# Telemetry_Unit.net
KiCad netlist of a schematic drawn in EAGLE
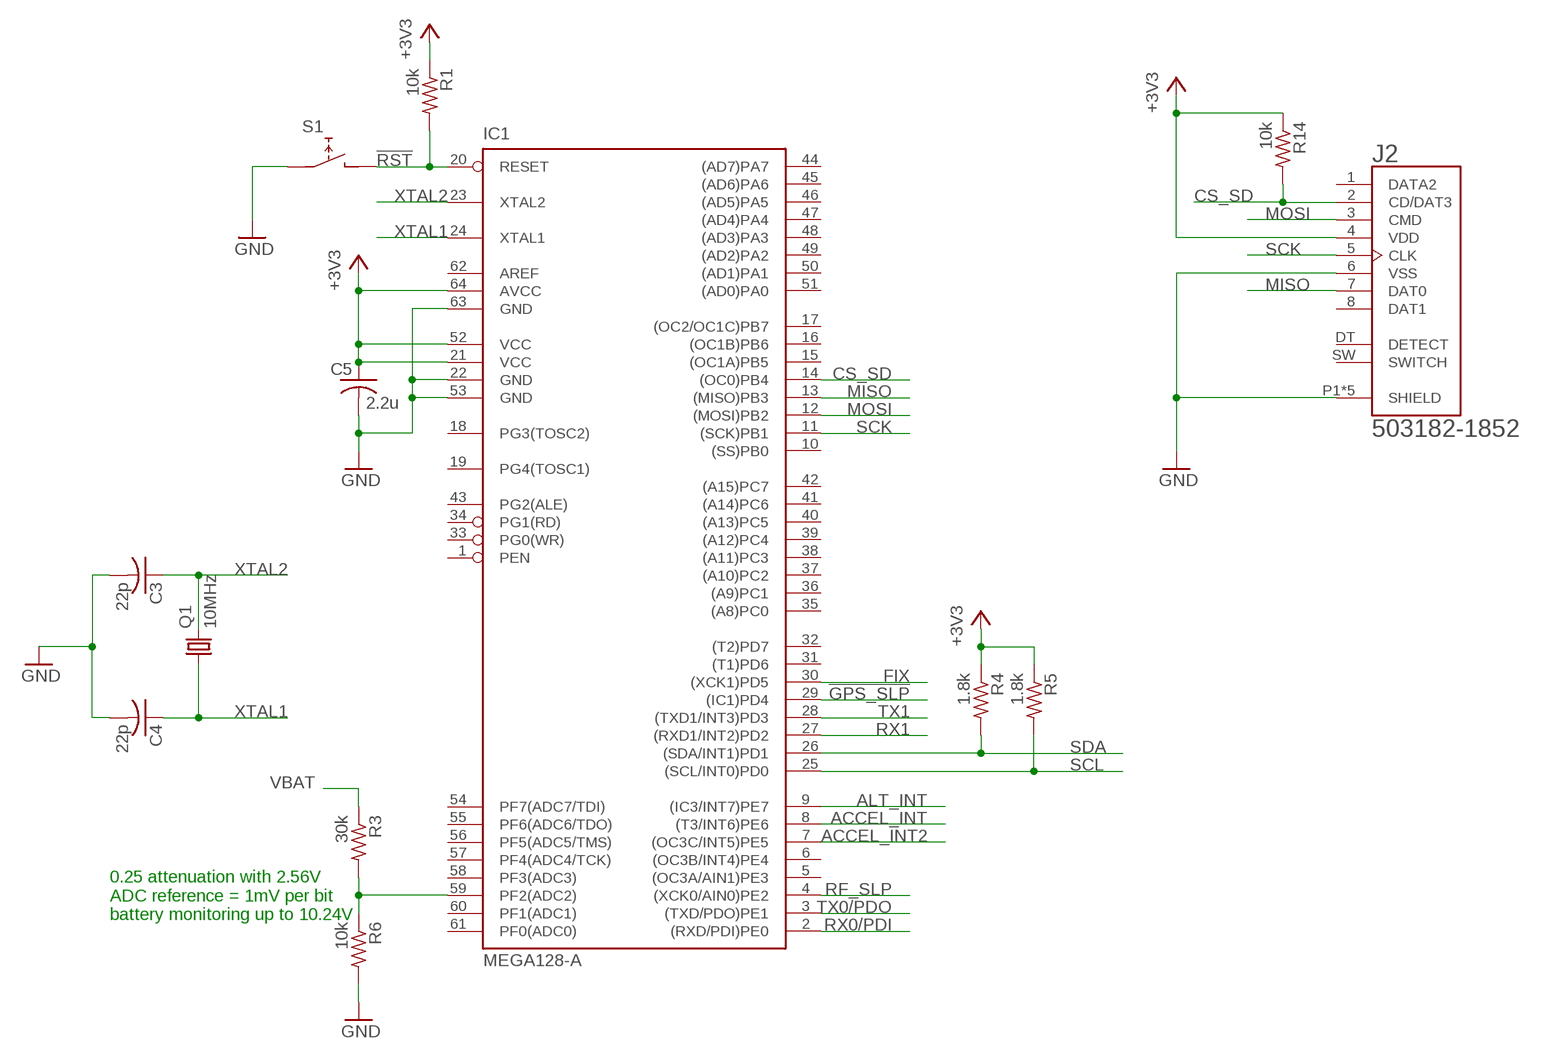
[diagram p0: schematic, sheet 1]
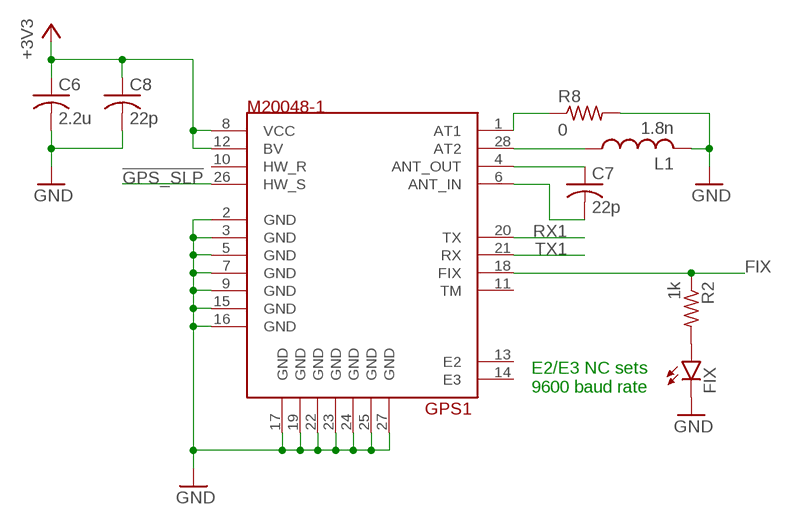
[diagram p1: schematic, sheet 2]
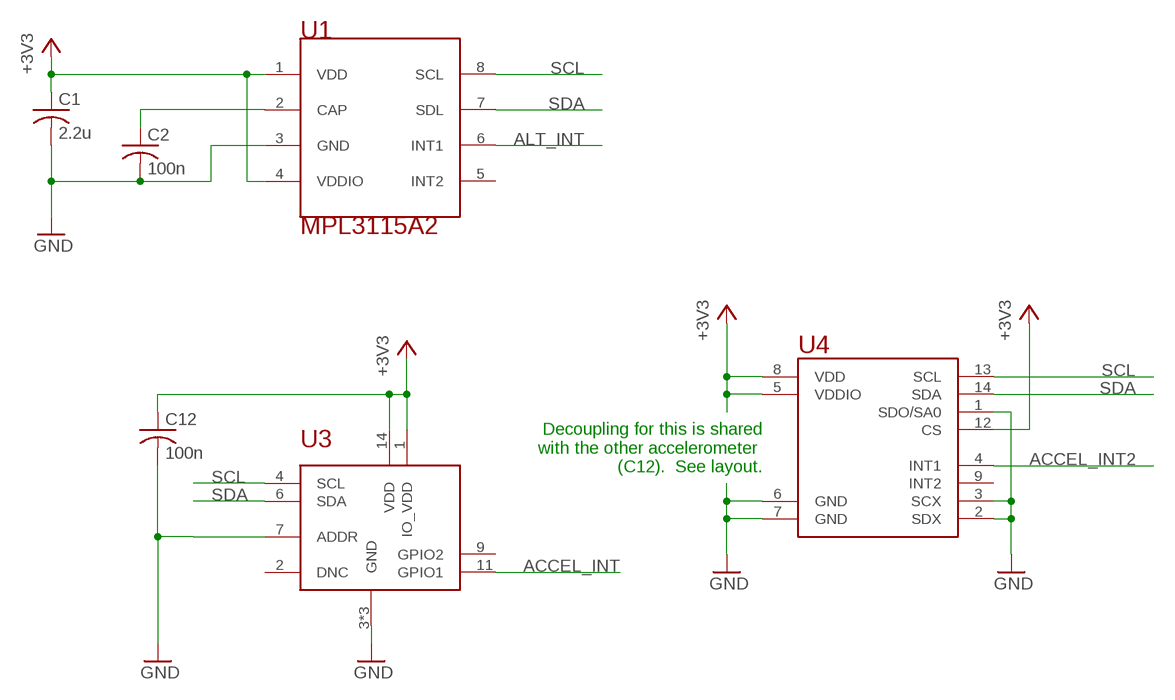
[diagram p2: schematic, sheet 3]
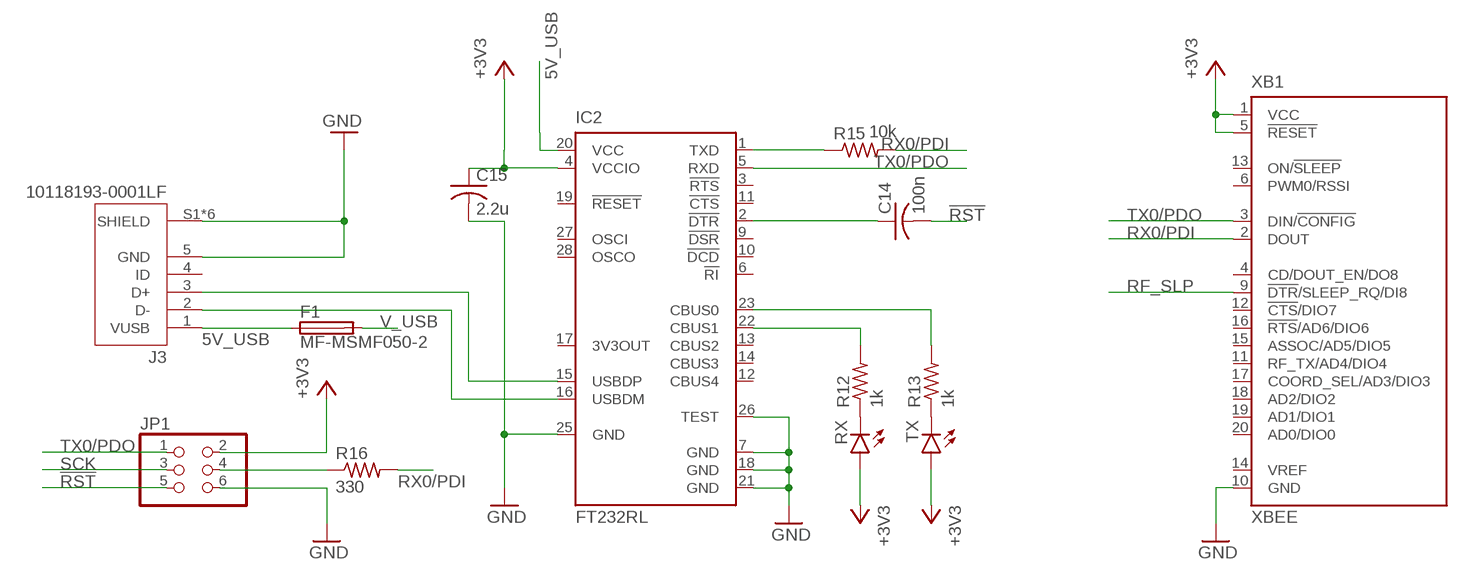
[diagram p3: schematic, sheet 4]
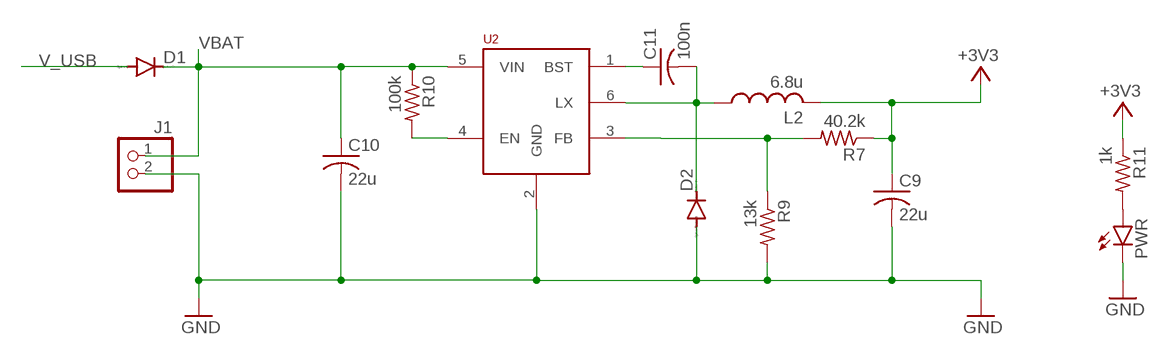
[diagram p4: schematic, sheet 5]

(export (version "E")
  (design (tool "Eeschema 10.0.6"))
  (components
    (comp (ref "C9")
      (value "22u")
      (footprint "eagle-import:C0805")
      (libsource (lib "eagle-import") (part "C-USC0805"))
    )
    (comp (ref "C10")
      (value "22u")
      (footprint "eagle-import:C0805")
      (libsource (lib "eagle-import") (part "C-USC0805"))
    )
    (comp (ref "C11")
      (value "100n")
      (footprint "eagle-import:C0603")
      (libsource (lib "eagle-import") (part "C-USC0603"))
    )
    (comp (ref "D1")
      (value "DIODE-SOD123")
      (footprint "eagle-import:SOD123")
      (libsource (lib "eagle-import") (part "DIODE-SOD123"))
    )
    (comp (ref "D2")
      (value "DIODE-SOD123")
      (footprint "eagle-import:SOD123")
      (libsource (lib "eagle-import") (part "DIODE-SOD123"))
    )
    (comp (ref "J1")
      (value "ST_2X1")
      (footprint "eagle-import:ST_2X1")
      (libsource (lib "eagle-import") (part "ST_2X1"))
    )
    (comp (ref "L2")
      (value "6.8u")
      (footprint "eagle-import:L1210")
      (libsource (lib "eagle-import") (part "L_SMALLL1210"))
    )
    (comp (ref "PWR")
      (value "LEDCHIP-LED0603")
      (footprint "eagle-import:CHIP-LED0603")
      (libsource (lib "eagle-import") (part "LEDCHIP-LED0603"))
    )
    (comp (ref "R7")
      (value "40.2k")
      (footprint "eagle-import:R0603")
      (libsource (lib "eagle-import") (part "resistor_348_R-US_R0603"))
    )
    (comp (ref "R9")
      (value "13k")
      (footprint "eagle-import:R0603")
      (libsource (lib "eagle-import") (part "resistor_348_R-US_R0603"))
    )
    (comp (ref "R10")
      (value "100k")
      (footprint "eagle-import:R0603")
      (libsource (lib "eagle-import") (part "resistor_348_R-US_R0603"))
    )
    (comp (ref "R11")
      (value "1k")
      (footprint "eagle-import:R0603")
      (libsource (lib "eagle-import") (part "resistor_348_R-US_R0603"))
    )
    (comp (ref "U2")
      (value "AOZ1280")
      (footprint "eagle-import:TSOT23-6")
      (libsource (lib "eagle-import") (part "AOZ1280"))
    )
    (comp (ref "C14")
      (value "100n")
      (footprint "eagle-import:C0603")
      (libsource (lib "eagle-import") (part "C-USC0603"))
    )
    (comp (ref "C15")
      (value "2.2u")
      (footprint "eagle-import:C0603")
      (libsource (lib "eagle-import") (part "C-USC0603"))
    )
    (comp (ref "F1")
      (value "MF-MSMF050-2")
      (footprint "eagle-import:FUSM1812X02")
      (fields (field (name "MF") "Bourns"))
      (libsource (lib "eagle-import") (part "MF-MSMF050-2"))
    )
    (comp (ref "IC2")
      (value "FT232RL")
      (footprint "eagle-import:SSOP28")
      (libsource (lib "eagle-import") (part "FT232RL"))
    )
    (comp (ref "J3")
      (value "10118193-0001LF")
      (footprint "eagle-import:FCI_10118193-0001LF")
      (fields (field (name "DIGI-KEY_PART_NUMBER") "609-4616-1-ND") (field (name "MF") "Amphenol ICC"))
      (libsource (lib "eagle-import") (part "10118193-0001LF"))
    )
    (comp (ref "JP1")
      (value "PINHD-2X3")
      (footprint "eagle-import:2X03")
      (libsource (lib "eagle-import") (part "PINHD-2X3"))
    )
    (comp (ref "R12")
      (value "1k")
      (footprint "eagle-import:R0603")
      (libsource (lib "eagle-import") (part "R-US_R0603"))
    )
    (comp (ref "R13")
      (value "1k")
      (footprint "eagle-import:R0603")
      (libsource (lib "eagle-import") (part "R-US_R0603"))
    )
    (comp (ref "R15")
      (value "10k")
      (footprint "eagle-import:R0603")
      (libsource (lib "eagle-import") (part "resistor_348_R-US_R0603"))
    )
    (comp (ref "R16")
      (value "330")
      (footprint "eagle-import:R0603")
      (libsource (lib "eagle-import") (part "resistor_348_R-US_R0603"))
    )
    (comp (ref "RX")
      (value "LEDCHIP-LED0603")
      (footprint "eagle-import:CHIP-LED0603")
      (libsource (lib "eagle-import") (part "LEDCHIP-LED0603"))
    )
    (comp (ref "TX")
      (value "LEDCHIP-LED0603")
      (footprint "eagle-import:CHIP-LED0603")
      (libsource (lib "eagle-import") (part "LEDCHIP-LED0603"))
    )
    (comp (ref "XB1")
      (value "XBEE")
      (footprint "eagle-import:XBEE")
      (fields (field (name "MPN") "XBP24-Z7UIT-004"))
      (libsource (lib "eagle-import") (part "XBEE"))
    )
    (comp (ref "C3")
      (value "22p")
      (footprint "eagle-import:C0603")
      (libsource (lib "eagle-import") (part "C-USC0603"))
    )
    (comp (ref "C4")
      (value "22p")
      (footprint "eagle-import:C0603")
      (libsource (lib "eagle-import") (part "C-USC0603"))
    )
    (comp (ref "C5")
      (value "2.2u")
      (footprint "eagle-import:C0603")
      (libsource (lib "eagle-import") (part "C-USC0603"))
    )
    (comp (ref "IC1")
      (value "MEGA128-A")
      (footprint "eagle-import:TQFP64")
      (fields (field (name "MPN") "ATMEGA128-16AU"))
      (libsource (lib "eagle-import") (part "MEGA128-A"))
    )
    (comp (ref "J2")
      (value "503182-1852")
      (footprint "eagle-import:MOLEX_503182-1852")
      (fields
        (field (name "DIGI-KEY_PART_NUMBER") "WM12834CT-ND")
        (field (name "MF") "Molex, LLC")
        (field (name "MP") "5031821852")
      )
      (libsource (lib "eagle-import") (part "503182-1852"))
    )
    (comp (ref "Q1")
      (value "10MHz")
      (footprint "eagle-import:3.2X2.5_KX-7")
      (libsource (lib "eagle-import") (part "KX-7"))
    )
    (comp (ref "R1")
      (value "10k")
      (footprint "eagle-import:R0603")
      (libsource (lib "eagle-import") (part "resistor_348_R-US_R0603"))
    )
    (comp (ref "R3")
      (value "30k")
      (footprint "eagle-import:R0603")
      (libsource (lib "eagle-import") (part "resistor_348_R-US_R0603"))
    )
    (comp (ref "R4")
      (value "1.8k")
      (footprint "eagle-import:R0603")
      (libsource (lib "eagle-import") (part "resistor_348_R-US_R0603"))
    )
    (comp (ref "R5")
      (value "1.8k")
      (footprint "eagle-import:R0603")
      (libsource (lib "eagle-import") (part "resistor_348_R-US_R0603"))
    )
    (comp (ref "R6")
      (value "10k")
      (footprint "eagle-import:R0603")
      (libsource (lib "eagle-import") (part "resistor_348_R-US_R0603"))
    )
    (comp (ref "R14")
      (value "10k")
      (footprint "eagle-import:R0603")
      (libsource (lib "eagle-import") (part "resistor_348_R-US_R0603"))
    )
    (comp (ref "S1")
      (value "TACT_SW_4.5MM")
      (footprint "eagle-import:TACT_SW_4.5MM")
      (libsource (lib "eagle-import") (part "TACT_SW_4.5MM"))
    )
    (comp (ref "C6")
      (value "2.2u")
      (footprint "eagle-import:C0603")
      (libsource (lib "eagle-import") (part "C-USC0603"))
    )
    (comp (ref "C7")
      (value "22p")
      (footprint "eagle-import:C0603")
      (libsource (lib "eagle-import") (part "C-USC0603"))
    )
    (comp (ref "C8")
      (value "22p")
      (footprint "eagle-import:C0603")
      (libsource (lib "eagle-import") (part "C-USC0603"))
    )
    (comp (ref "FIX")
      (value "LEDCHIP-LED0603")
      (footprint "eagle-import:CHIP-LED0603")
      (libsource (lib "eagle-import") (part "LEDCHIP-LED0603"))
    )
    (comp (ref "GPS1")
      (value "M20048-1")
      (footprint "eagle-import:M20048-1")
      (libsource (lib "eagle-import") (part "M20048-1"))
    )
    (comp (ref "L1")
      (value "1.8n")
      (footprint "eagle-import:L0603")
      (libsource (lib "eagle-import") (part "L_SMALLL0603"))
    )
    (comp (ref "R2")
      (value "1k")
      (footprint "eagle-import:R0603")
      (libsource (lib "eagle-import") (part "resistor_348_R-US_R0603"))
    )
    (comp (ref "R8")
      (value "0")
      (footprint "eagle-import:R0603")
      (libsource (lib "eagle-import") (part "resistor_348_R-US_R0603"))
    )
    (comp (ref "C1")
      (value "2.2u")
      (footprint "eagle-import:C0603")
      (libsource (lib "eagle-import") (part "C-USC0603"))
    )
    (comp (ref "C2")
      (value "100n")
      (footprint "eagle-import:C0603")
      (libsource (lib "eagle-import") (part "C-USC0603"))
    )
    (comp (ref "C12")
      (value "100n")
      (footprint "eagle-import:C0603")
      (libsource (lib "eagle-import") (part "C-USC0603"))
    )
    (comp (ref "U1")
      (value "MPL3115A2")
      (footprint "eagle-import:LGA8")
      (libsource (lib "eagle-import") (part "MPL3115A2"))
    )
    (comp (ref "U3")
      (value "KMX63-1055")
      (footprint "eagle-import:LGA16_3X3")
      (libsource (lib "eagle-import") (part "KMX63-1055"))
    )
    (comp (ref "U4")
      (value "LSM6DS3")
      (footprint "eagle-import:14-LGA")
      (libsource (lib "eagle-import") (part "LSM6DS3"))
    )
  )
  (nets
    (net (code "1") (name "+3V3") (class "Default")
      (node (ref "C1") (pin "1") (pinfunction "1_1") (pintype "passive"))
      (node (ref "C12") (pin "1") (pinfunction "1_1") (pintype "passive"))
      (node (ref "C15") (pin "1") (pinfunction "1_1") (pintype "passive"))
      (node (ref "C5") (pin "1") (pinfunction "1_1") (pintype "passive"))
      (node (ref "C6") (pin "1") (pinfunction "1_1") (pintype "passive"))
      (node (ref "C8") (pin "1") (pinfunction "1_1") (pintype "passive"))
      (node (ref "C9") (pin "1") (pinfunction "1_1") (pintype "passive"))
      (node (ref "GPS1") (pin "12") (pinfunction "BV_12") (pintype "bidirectional"))
      (node (ref "GPS1") (pin "8") (pinfunction "VCC_8") (pintype "bidirectional"))
      (node (ref "IC1") (pin "21") (pinfunction "VCC_21") (pintype "power_in"))
      (node (ref "IC1") (pin "52") (pinfunction "VCC_52") (pintype "power_in"))
      (node (ref "IC1") (pin "64") (pinfunction "AVCC_64") (pintype "power_in"))
      (node (ref "IC2") (pin "4") (pinfunction "VCCIO_4") (pintype "power_in"))
      (node (ref "J2") (pin "4") (pinfunction "VDD_4") (pintype "power_in"))
      (node (ref "JP1") (pin "2") (pinfunction "2_2") (pintype "passive"))
      (node (ref "L2") (pin "2") (pinfunction "2_2") (pintype "passive"))
      (node (ref "R1") (pin "1") (pinfunction "1_1") (pintype "passive"))
      (node (ref "R11") (pin "1") (pinfunction "1_1") (pintype "passive"))
      (node (ref "R14") (pin "1") (pinfunction "1_1") (pintype "passive"))
      (node (ref "R4") (pin "1") (pinfunction "1_1") (pintype "passive"))
      (node (ref "R5") (pin "1") (pinfunction "1_1") (pintype "passive"))
      (node (ref "R7") (pin "1") (pinfunction "1_1") (pintype "passive"))
      (node (ref "RX") (pin "A") (pinfunction "A_A") (pintype "passive"))
      (node (ref "TX") (pin "A") (pinfunction "A_A") (pintype "passive"))
      (node (ref "U1") (pin "1") (pinfunction "VDD_1") (pintype "bidirectional"))
      (node (ref "U1") (pin "4") (pinfunction "VDDIO_4") (pintype "bidirectional"))
      (node (ref "U3") (pin "1") (pinfunction "IO_VDD_1") (pintype "bidirectional"))
      (node (ref "U3") (pin "14") (pinfunction "VDD_14") (pintype "bidirectional"))
      (node (ref "U4") (pin "12") (pinfunction "CS_12") (pintype "bidirectional"))
      (node (ref "U4") (pin "5") (pinfunction "VDDIO_5") (pintype "bidirectional"))
      (node (ref "U4") (pin "8") (pinfunction "VDD_8") (pintype "bidirectional"))
      (node (ref "XB1") (pin "1") (pinfunction "VCC_1") (pintype "power_in"))
      (node (ref "XB1") (pin "5") (pinfunction "~{RESET}_5") (pintype "input"))
    )
    (net (code "2") (name "5V_USB") (class "Default")
      (node (ref "F1") (pin "1") (pinfunction "1_1") (pintype "passive"))
      (node (ref "IC2") (pin "20") (pinfunction "VCC_20") (pintype "power_in"))
      (node (ref "J3") (pin "1") (pinfunction "VUSB_1") (pintype "passive"))
    )
    (net (code "3") (name "ACCEL_INT") (class "Default")
      (node (ref "IC1") (pin "8") (pinfunction "(T3/INT6)PE6_8") (pintype "bidirectional"))
      (node (ref "U3") (pin "11") (pinfunction "GPIO1_11") (pintype "bidirectional"))
    )
    (net (code "4") (name "ACCEL_INT2") (class "Default")
      (node (ref "IC1") (pin "7") (pinfunction "(OC3C/INT5)PE5_7") (pintype "bidirectional"))
      (node (ref "U4") (pin "4") (pinfunction "INT1_4") (pintype "bidirectional"))
    )
    (net (code "5") (name "ALT_INT") (class "Default")
      (node (ref "IC1") (pin "9") (pinfunction "(IC3/INT7)PE7_9") (pintype "bidirectional"))
      (node (ref "U1") (pin "6") (pinfunction "INT1_6") (pintype "bidirectional"))
    )
    (net (code "6") (name "CS_SD") (class "Default")
      (node (ref "IC1") (pin "14") (pinfunction "(OC0)PB4_14") (pintype "bidirectional"))
      (node (ref "J2") (pin "2") (pinfunction "CD/DAT3_2") (pintype "bidirectional"))
      (node (ref "R14") (pin "2") (pinfunction "2_2") (pintype "passive"))
    )
    (net (code "7") (name "FIX") (class "Default")
      (node (ref "GPS1") (pin "18") (pinfunction "FIX_18") (pintype "bidirectional"))
      (node (ref "IC1") (pin "30") (pinfunction "(XCK1)PD5_30") (pintype "bidirectional"))
      (node (ref "R2") (pin "1") (pinfunction "1_1") (pintype "passive"))
    )
    (net (code "8") (name "GND") (class "Default")
      (node (ref "C1") (pin "2") (pinfunction "2_2") (pintype "passive"))
      (node (ref "C10") (pin "2") (pinfunction "2_2") (pintype "passive"))
      (node (ref "C12") (pin "2") (pinfunction "2_2") (pintype "passive"))
      (node (ref "C15") (pin "2") (pinfunction "2_2") (pintype "passive"))
      (node (ref "C2") (pin "2") (pinfunction "2_2") (pintype "passive"))
      (node (ref "C3") (pin "2") (pinfunction "2_2") (pintype "passive"))
      (node (ref "C4") (pin "2") (pinfunction "2_2") (pintype "passive"))
      (node (ref "C5") (pin "2") (pinfunction "2_2") (pintype "passive"))
      (node (ref "C6") (pin "2") (pinfunction "2_2") (pintype "passive"))
      (node (ref "C8") (pin "2") (pinfunction "2_2") (pintype "passive"))
      (node (ref "C9") (pin "2") (pinfunction "2_2") (pintype "passive"))
      (node (ref "D2") (pin "A") (pinfunction "A_A") (pintype "passive"))
      (node (ref "FIX") (pin "C") (pinfunction "C_C") (pintype "passive"))
      (node (ref "GPS1") (pin "15") (pinfunction "GND_15") (pintype "bidirectional"))
      (node (ref "GPS1") (pin "16") (pinfunction "GND_16") (pintype "bidirectional"))
      (node (ref "GPS1") (pin "17") (pinfunction "GND_17") (pintype "bidirectional"))
      (node (ref "GPS1") (pin "19") (pinfunction "GND_19") (pintype "bidirectional"))
      (node (ref "GPS1") (pin "2") (pinfunction "GND_2") (pintype "bidirectional"))
      (node (ref "GPS1") (pin "22") (pinfunction "GND_22") (pintype "bidirectional"))
      (node (ref "GPS1") (pin "23") (pinfunction "GND_23") (pintype "bidirectional"))
      (node (ref "GPS1") (pin "24") (pinfunction "GND_24") (pintype "bidirectional"))
      (node (ref "GPS1") (pin "25") (pinfunction "GND_25") (pintype "bidirectional"))
      (node (ref "GPS1") (pin "27") (pinfunction "GND_27") (pintype "bidirectional"))
      (node (ref "GPS1") (pin "3") (pinfunction "GND_3") (pintype "bidirectional"))
      (node (ref "GPS1") (pin "5") (pinfunction "GND_5") (pintype "bidirectional"))
      (node (ref "GPS1") (pin "7") (pinfunction "GND_7") (pintype "bidirectional"))
      (node (ref "GPS1") (pin "9") (pinfunction "GND_9") (pintype "bidirectional"))
      (node (ref "IC1") (pin "22") (pinfunction "GND_22") (pintype "power_in"))
      (node (ref "IC1") (pin "53") (pinfunction "GND_53") (pintype "power_in"))
      (node (ref "IC1") (pin "63") (pinfunction "GND_63") (pintype "power_in"))
      (node (ref "IC2") (pin "18") (pinfunction "GND_18") (pintype "power_in"))
      (node (ref "IC2") (pin "21") (pinfunction "GND_21") (pintype "power_in"))
      (node (ref "IC2") (pin "25") (pinfunction "GND_25") (pintype "power_in"))
      (node (ref "IC2") (pin "26") (pinfunction "TEST_26") (pintype "input"))
      (node (ref "IC2") (pin "7") (pinfunction "GND_7") (pintype "power_in"))
      (node (ref "J1") (pin "2") (pinfunction "2_2") (pintype "passive"))
      (node (ref "J2") (pin "6") (pinfunction "VSS_6") (pintype "power_in"))
      (node (ref "J2") (pin "P1") (pinfunction "SHIELD_P1") (pintype "passive"))
      (node (ref "J2") (pin "P2") (pinfunction "SHIELD_P2") (pintype "passive"))
      (node (ref "J2") (pin "P3") (pinfunction "SHIELD_P3") (pintype "passive"))
      (node (ref "J2") (pin "P4") (pinfunction "SHIELD_P4") (pintype "passive"))
      (node (ref "J2") (pin "P5") (pinfunction "SHIELD_P5") (pintype "passive"))
      (node (ref "J3") (pin "5") (pinfunction "GND_5") (pintype "passive"))
      (node (ref "J3") (pin "S1") (pinfunction "SHIELD_S1") (pintype "passive"))
      (node (ref "J3") (pin "S2") (pinfunction "SHIELD_S2") (pintype "passive"))
      (node (ref "J3") (pin "S3") (pinfunction "SHIELD_S3") (pintype "passive"))
      (node (ref "J3") (pin "S4") (pinfunction "SHIELD_S4") (pintype "passive"))
      (node (ref "J3") (pin "S5") (pinfunction "SHIELD_S5") (pintype "passive"))
      (node (ref "J3") (pin "S6") (pinfunction "SHIELD_S6") (pintype "passive"))
      (node (ref "JP1") (pin "6") (pinfunction "6_6") (pintype "passive"))
      (node (ref "L1") (pin "2") (pinfunction "2_2") (pintype "passive"))
      (node (ref "PWR") (pin "C") (pinfunction "C_C") (pintype "passive"))
      (node (ref "R6") (pin "2") (pinfunction "2_2") (pintype "passive"))
      (node (ref "R8") (pin "2") (pinfunction "2_2") (pintype "passive"))
      (node (ref "R9") (pin "2") (pinfunction "2_2") (pintype "passive"))
      (node (ref "S1") (pin "P1@1") (pinfunction "0_P1@1") (pintype "passive"))
      (node (ref "S1") (pin "P1@2") (pinfunction "0_P1@2") (pintype "passive"))
      (node (ref "U1") (pin "3") (pinfunction "GND_3") (pintype "bidirectional"))
      (node (ref "U2") (pin "2") (pinfunction "GND_2") (pintype "bidirectional"))
      (node (ref "U3") (pin "12") (pinfunction "GND_12") (pintype "bidirectional"))
      (node (ref "U3") (pin "3") (pinfunction "GND_3") (pintype "bidirectional"))
      (node (ref "U3") (pin "5") (pinfunction "GND_5") (pintype "bidirectional"))
      (node (ref "U3") (pin "7") (pinfunction "ADDR_7") (pintype "bidirectional"))
      (node (ref "U4") (pin "1") (pinfunction "SDO/SA0_1") (pintype "bidirectional"))
      (node (ref "U4") (pin "2") (pinfunction "SDX_2") (pintype "bidirectional"))
      (node (ref "U4") (pin "3") (pinfunction "SCX_3") (pintype "bidirectional"))
      (node (ref "U4") (pin "6") (pinfunction "GND_6") (pintype "bidirectional"))
      (node (ref "U4") (pin "7") (pinfunction "GND_7") (pintype "bidirectional"))
      (node (ref "XB1") (pin "10") (pinfunction "GND_10") (pintype "power_in"))
    )
    (net (code "9") (name "MISO") (class "Default")
      (node (ref "IC1") (pin "13") (pinfunction "(MISO)PB3_13") (pintype "bidirectional"))
      (node (ref "J2") (pin "7") (pinfunction "DAT0_7") (pintype "bidirectional"))
    )
    (net (code "10") (name "MOSI") (class "Default")
      (node (ref "IC1") (pin "12") (pinfunction "(MOSI)PB2_12") (pintype "bidirectional"))
      (node (ref "J2") (pin "3") (pinfunction "CMD_3") (pintype "bidirectional"))
    )
    (net (code "11") (name "Net-(FIX-PadA)") (class "Default")
      (node (ref "FIX") (pin "A") (pinfunction "A_A") (pintype "passive"))
      (node (ref "R2") (pin "2") (pinfunction "2_2") (pintype "passive"))
    )
    (net (code "12") (name "Net-(GPS1-ANT_IN)") (class "Default")
      (node (ref "C7") (pin "2") (pinfunction "2_2") (pintype "passive"))
      (node (ref "GPS1") (pin "6") (pinfunction "ANT_IN_6") (pintype "bidirectional"))
    )
    (net (code "13") (name "Net-(GPS1-ANT_OUT)") (class "Default")
      (node (ref "C7") (pin "1") (pinfunction "1_1") (pintype "passive"))
      (node (ref "GPS1") (pin "4") (pinfunction "ANT_OUT_4") (pintype "bidirectional"))
    )
    (net (code "14") (name "Net-(GPS1-AT1)") (class "Default")
      (node (ref "GPS1") (pin "1") (pinfunction "AT1_1") (pintype "bidirectional"))
      (node (ref "R8") (pin "1") (pinfunction "1_1") (pintype "passive"))
    )
    (net (code "15") (name "Net-(GPS1-AT2)") (class "Default")
      (node (ref "GPS1") (pin "28") (pinfunction "AT2_28") (pintype "bidirectional"))
      (node (ref "L1") (pin "1") (pinfunction "1_1") (pintype "passive"))
    )
    (net (code "16") (name "Net-(IC1-PF2(ADC2))") (class "Default")
      (node (ref "IC1") (pin "59") (pinfunction "PF2(ADC2)_59") (pintype "input"))
      (node (ref "R3") (pin "2") (pinfunction "2_2") (pintype "passive"))
      (node (ref "R6") (pin "1") (pinfunction "1_1") (pintype "passive"))
    )
    (net (code "17") (name "Net-(IC2-CBUS0)") (class "Default")
      (node (ref "IC2") (pin "23") (pinfunction "CBUS0_23") (pintype "bidirectional"))
      (node (ref "R13") (pin "2") (pinfunction "2_2") (pintype "passive"))
    )
    (net (code "18") (name "Net-(IC2-CBUS1)") (class "Default")
      (node (ref "IC2") (pin "22") (pinfunction "CBUS1_22") (pintype "bidirectional"))
      (node (ref "R12") (pin "2") (pinfunction "2_2") (pintype "passive"))
    )
    (net (code "19") (name "Net-(IC2-TXD)") (class "Default")
      (node (ref "IC2") (pin "1") (pinfunction "TXD_1") (pintype "output"))
      (node (ref "R15") (pin "1") (pinfunction "1_1") (pintype "passive"))
    )
    (net (code "20") (name "Net-(IC2-USBDM)") (class "Default")
      (node (ref "IC2") (pin "16") (pinfunction "USBDM_16") (pintype "bidirectional"))
      (node (ref "J3") (pin "2") (pinfunction "D-_2") (pintype "passive"))
    )
    (net (code "21") (name "Net-(IC2-USBDP)") (class "Default")
      (node (ref "IC2") (pin "15") (pinfunction "USBDP_15") (pintype "bidirectional"))
      (node (ref "J3") (pin "3") (pinfunction "D+_3") (pintype "passive"))
    )
    (net (code "22") (name "Net-(IC2-~{DTR})") (class "Default")
      (node (ref "C14") (pin "1") (pinfunction "1_1") (pintype "passive"))
      (node (ref "IC2") (pin "2") (pinfunction "~{DTR}_2") (pintype "output"))
    )
    (net (code "23") (name "Net-(JP1-Pad4)") (class "Default")
      (node (ref "JP1") (pin "4") (pinfunction "4_4") (pintype "passive"))
      (node (ref "R16") (pin "1") (pinfunction "1_1") (pintype "passive"))
    )
    (net (code "24") (name "Net-(PWR-PadA)") (class "Default")
      (node (ref "PWR") (pin "A") (pinfunction "A_A") (pintype "passive"))
      (node (ref "R11") (pin "2") (pinfunction "2_2") (pintype "passive"))
    )
    (net (code "25") (name "Net-(R12-Pad1)") (class "Default")
      (node (ref "R12") (pin "1") (pinfunction "1_1") (pintype "passive"))
      (node (ref "RX") (pin "C") (pinfunction "C_C") (pintype "passive"))
    )
    (net (code "26") (name "Net-(R13-Pad1)") (class "Default")
      (node (ref "R13") (pin "1") (pinfunction "1_1") (pintype "passive"))
      (node (ref "TX") (pin "C") (pinfunction "C_C") (pintype "passive"))
    )
    (net (code "27") (name "Net-(U1-CAP)") (class "Default")
      (node (ref "C2") (pin "1") (pinfunction "1_1") (pintype "passive"))
      (node (ref "U1") (pin "2") (pinfunction "CAP_2") (pintype "bidirectional"))
    )
    (net (code "28") (name "Net-(U2-BST)") (class "Default")
      (node (ref "C11") (pin "1") (pinfunction "1_1") (pintype "passive"))
      (node (ref "U2") (pin "1") (pinfunction "BST_1") (pintype "bidirectional"))
    )
    (net (code "29") (name "Net-(U2-EN)") (class "Default")
      (node (ref "R10") (pin "2") (pinfunction "2_2") (pintype "passive"))
      (node (ref "U2") (pin "4") (pinfunction "EN_4") (pintype "bidirectional"))
    )
    (net (code "30") (name "Net-(U2-FB)") (class "Default")
      (node (ref "R7") (pin "2") (pinfunction "2_2") (pintype "passive"))
      (node (ref "R9") (pin "1") (pinfunction "1_1") (pintype "passive"))
      (node (ref "U2") (pin "3") (pinfunction "FB_3") (pintype "bidirectional"))
    )
    (net (code "31") (name "Net-(U2-LX)") (class "Default")
      (node (ref "C11") (pin "2") (pinfunction "2_2") (pintype "passive"))
      (node (ref "D2") (pin "C") (pinfunction "C_C") (pintype "passive"))
      (node (ref "L2") (pin "1") (pinfunction "1_1") (pintype "passive"))
      (node (ref "U2") (pin "6") (pinfunction "LX_6") (pintype "bidirectional"))
    )
    (net (code "32") (name "RF_SLP") (class "Default")
      (node (ref "IC1") (pin "4") (pinfunction "(XCK0/AIN0)PE2_4") (pintype "bidirectional"))
      (node (ref "XB1") (pin "9") (pinfunction "~{DTR}/SLEEP_RQ/DI8_9") (pintype "bidirectional"))
    )
    (net (code "33") (name "RX0{slash}PDI") (class "Default")
      (node (ref "IC1") (pin "2") (pinfunction "(RXD/PDI)PE0_2") (pintype "bidirectional"))
      (node (ref "R15") (pin "2") (pinfunction "2_2") (pintype "passive"))
      (node (ref "R16") (pin "2") (pinfunction "2_2") (pintype "passive"))
      (node (ref "XB1") (pin "2") (pinfunction "DOUT_2") (pintype "output"))
    )
    (net (code "34") (name "RX1") (class "Default")
      (node (ref "GPS1") (pin "20") (pinfunction "TX_20") (pintype "bidirectional"))
      (node (ref "IC1") (pin "27") (pinfunction "(RXD1/INT2)PD2_27") (pintype "bidirectional"))
    )
    (net (code "35") (name "SCK") (class "Default")
      (node (ref "IC1") (pin "11") (pinfunction "(SCK)PB1_11") (pintype "bidirectional"))
      (node (ref "J2") (pin "5") (pinfunction "CLK_5") (pintype "bidirectional"))
      (node (ref "JP1") (pin "3") (pinfunction "3_3") (pintype "passive"))
    )
    (net (code "36") (name "SCL") (class "Default")
      (node (ref "IC1") (pin "25") (pinfunction "(SCL/INT0)PD0_25") (pintype "bidirectional"))
      (node (ref "R5") (pin "2") (pinfunction "2_2") (pintype "passive"))
      (node (ref "U1") (pin "8") (pinfunction "SCL_8") (pintype "bidirectional"))
      (node (ref "U3") (pin "4") (pinfunction "SCL_4") (pintype "bidirectional"))
      (node (ref "U4") (pin "13") (pinfunction "SCL_13") (pintype "bidirectional"))
    )
    (net (code "37") (name "SDA") (class "Default")
      (node (ref "IC1") (pin "26") (pinfunction "(SDA/INT1)PD1_26") (pintype "bidirectional"))
      (node (ref "R4") (pin "2") (pinfunction "2_2") (pintype "passive"))
      (node (ref "U1") (pin "7") (pinfunction "SDL_7") (pintype "bidirectional"))
      (node (ref "U3") (pin "6") (pinfunction "SDA_6") (pintype "bidirectional"))
      (node (ref "U4") (pin "14") (pinfunction "SDA_14") (pintype "bidirectional"))
    )
    (net (code "38") (name "TX0{slash}PDO") (class "Default")
      (node (ref "IC1") (pin "3") (pinfunction "(TXD/PDO)PE1_3") (pintype "bidirectional"))
      (node (ref "IC2") (pin "5") (pinfunction "RXD_5") (pintype "input"))
      (node (ref "JP1") (pin "1") (pinfunction "1_1") (pintype "passive"))
      (node (ref "XB1") (pin "3") (pinfunction "DIN/~{CONFIG}_3") (pintype "input"))
    )
    (net (code "39") (name "TX1") (class "Default")
      (node (ref "GPS1") (pin "21") (pinfunction "RX_21") (pintype "bidirectional"))
      (node (ref "IC1") (pin "28") (pinfunction "(TXD1/INT3)PD3_28") (pintype "bidirectional"))
    )
    (net (code "40") (name "VBAT") (class "Default")
      (node (ref "C10") (pin "1") (pinfunction "1_1") (pintype "passive"))
      (node (ref "D1") (pin "C") (pinfunction "C_C") (pintype "passive"))
      (node (ref "J1") (pin "1") (pinfunction "1_1") (pintype "passive"))
      (node (ref "R10") (pin "1") (pinfunction "1_1") (pintype "passive"))
      (node (ref "R3") (pin "1") (pinfunction "1_1") (pintype "passive"))
      (node (ref "U2") (pin "5") (pinfunction "VIN_5") (pintype "bidirectional"))
    )
    (net (code "41") (name "V_USB") (class "Default")
      (node (ref "D1") (pin "A") (pinfunction "A_A") (pintype "passive"))
      (node (ref "F1") (pin "2") (pinfunction "2_2") (pintype "passive"))
    )
    (net (code "42") (name "XTAL1") (class "Default")
      (node (ref "C4") (pin "1") (pinfunction "1_1") (pintype "passive"))
      (node (ref "IC1") (pin "24") (pinfunction "XTAL1_24") (pintype "bidirectional"))
      (node (ref "Q1") (pin "1") (pinfunction "1_1") (pintype "passive"))
    )
    (net (code "43") (name "XTAL2") (class "Default")
      (node (ref "C3") (pin "1") (pinfunction "1_1") (pintype "passive"))
      (node (ref "IC1") (pin "23") (pinfunction "XTAL2_23") (pintype "bidirectional"))
      (node (ref "Q1") (pin "3") (pinfunction "2_3") (pintype "passive"))
    )
    (net (code "44") (name "unconnected-(GPS1-E2-Pad13)") (class "Default")
      (node (ref "GPS1") (pin "13") (pinfunction "E2_13") (pintype "bidirectional"))
    )
    (net (code "45") (name "unconnected-(GPS1-E3-Pad14)") (class "Default")
      (node (ref "GPS1") (pin "14") (pinfunction "E3_14") (pintype "bidirectional"))
    )
    (net (code "46") (name "unconnected-(GPS1-HW_R-Pad10)") (class "Default")
      (node (ref "GPS1") (pin "10") (pinfunction "HW_R_10") (pintype "bidirectional"))
    )
    (net (code "47") (name "unconnected-(GPS1-TM-Pad11)") (class "Default")
      (node (ref "GPS1") (pin "11") (pinfunction "TM_11") (pintype "bidirectional"))
    )
    (net (code "48") (name "unconnected-(IC1-(A8)PC0-Pad35)") (class "Default")
      (node (ref "IC1") (pin "35") (pinfunction "(A8)PC0_35") (pintype "output"))
    )
    (net (code "49") (name "unconnected-(IC1-(A9)PC1-Pad36)") (class "Default")
      (node (ref "IC1") (pin "36") (pinfunction "(A9)PC1_36") (pintype "output"))
    )
    (net (code "50") (name "unconnected-(IC1-(A10)PC2-Pad37)") (class "Default")
      (node (ref "IC1") (pin "37") (pinfunction "(A10)PC2_37") (pintype "output"))
    )
    (net (code "51") (name "unconnected-(IC1-(A11)PC3-Pad38)") (class "Default")
      (node (ref "IC1") (pin "38") (pinfunction "(A11)PC3_38") (pintype "output"))
    )
    (net (code "52") (name "unconnected-(IC1-(A12)PC4-Pad39)") (class "Default")
      (node (ref "IC1") (pin "39") (pinfunction "(A12)PC4_39") (pintype "output"))
    )
    (net (code "53") (name "unconnected-(IC1-(A13)PC5-Pad40)") (class "Default")
      (node (ref "IC1") (pin "40") (pinfunction "(A13)PC5_40") (pintype "output"))
    )
    (net (code "54") (name "unconnected-(IC1-(A14)PC6-Pad41)") (class "Default")
      (node (ref "IC1") (pin "41") (pinfunction "(A14)PC6_41") (pintype "output"))
    )
    (net (code "55") (name "unconnected-(IC1-(A15)PC7-Pad42)") (class "Default")
      (node (ref "IC1") (pin "42") (pinfunction "(A15)PC7_42") (pintype "output"))
    )
    (net (code "56") (name "unconnected-(IC1-(AD0)PA0-Pad51)") (class "Default")
      (node (ref "IC1") (pin "51") (pinfunction "(AD0)PA0_51") (pintype "bidirectional"))
    )
    (net (code "57") (name "unconnected-(IC1-(AD1)PA1-Pad50)") (class "Default")
      (node (ref "IC1") (pin "50") (pinfunction "(AD1)PA1_50") (pintype "bidirectional"))
    )
    (net (code "58") (name "unconnected-(IC1-(AD2)PA2-Pad49)") (class "Default")
      (node (ref "IC1") (pin "49") (pinfunction "(AD2)PA2_49") (pintype "bidirectional"))
    )
    (net (code "59") (name "unconnected-(IC1-(AD3)PA3-Pad48)") (class "Default")
      (node (ref "IC1") (pin "48") (pinfunction "(AD3)PA3_48") (pintype "bidirectional"))
    )
    (net (code "60") (name "unconnected-(IC1-(AD4)PA4-Pad47)") (class "Default")
      (node (ref "IC1") (pin "47") (pinfunction "(AD4)PA4_47") (pintype "bidirectional"))
    )
    (net (code "61") (name "unconnected-(IC1-(AD5)PA5-Pad46)") (class "Default")
      (node (ref "IC1") (pin "46") (pinfunction "(AD5)PA5_46") (pintype "bidirectional"))
    )
    (net (code "62") (name "unconnected-(IC1-(AD6)PA6-Pad45)") (class "Default")
      (node (ref "IC1") (pin "45") (pinfunction "(AD6)PA6_45") (pintype "bidirectional"))
    )
    (net (code "63") (name "unconnected-(IC1-(AD7)PA7-Pad44)") (class "Default")
      (node (ref "IC1") (pin "44") (pinfunction "(AD7)PA7_44") (pintype "bidirectional"))
    )
    (net (code "64") (name "unconnected-(IC1-(OC1A)PB5-Pad15)") (class "Default")
      (node (ref "IC1") (pin "15") (pinfunction "(OC1A)PB5_15") (pintype "bidirectional"))
    )
    (net (code "65") (name "unconnected-(IC1-(OC1B)PB6-Pad16)") (class "Default")
      (node (ref "IC1") (pin "16") (pinfunction "(OC1B)PB6_16") (pintype "bidirectional"))
    )
    (net (code "66") (name "unconnected-(IC1-(OC2{slash}OC1C)PB7-Pad17)") (class "Default")
      (node (ref "IC1") (pin "17") (pinfunction "(OC2/OC1C)PB7_17") (pintype "bidirectional"))
    )
    (net (code "67") (name "unconnected-(IC1-(OC3A{slash}AIN1)PE3-Pad5)") (class "Default")
      (node (ref "IC1") (pin "5") (pinfunction "(OC3A/AIN1)PE3_5") (pintype "bidirectional"))
    )
    (net (code "68") (name "unconnected-(IC1-(OC3B{slash}INT4)PE4-Pad6)") (class "Default")
      (node (ref "IC1") (pin "6") (pinfunction "(OC3B/INT4)PE4_6") (pintype "bidirectional"))
    )
    (net (code "69") (name "unconnected-(IC1-(SS)PB0-Pad10)") (class "Default")
      (node (ref "IC1") (pin "10") (pinfunction "(SS)PB0_10") (pintype "bidirectional"))
    )
    (net (code "70") (name "unconnected-(IC1-(T1)PD6-Pad31)") (class "Default")
      (node (ref "IC1") (pin "31") (pinfunction "(T1)PD6_31") (pintype "bidirectional"))
    )
    (net (code "71") (name "unconnected-(IC1-(T2)PD7-Pad32)") (class "Default")
      (node (ref "IC1") (pin "32") (pinfunction "(T2)PD7_32") (pintype "bidirectional"))
    )
    (net (code "72") (name "unconnected-(IC1-AREF-Pad62)") (class "Default")
      (node (ref "IC1") (pin "62") (pinfunction "AREF_62") (pintype "passive"))
    )
    (net (code "73") (name "unconnected-(IC1-PEN-Pad1)") (class "Default")
      (node (ref "IC1") (pin "1") (pinfunction "PEN_1") (pintype "input"))
    )
    (net (code "74") (name "unconnected-(IC1-PF0(ADC0)-Pad61)") (class "Default")
      (node (ref "IC1") (pin "61") (pinfunction "PF0(ADC0)_61") (pintype "input"))
    )
    (net (code "75") (name "unconnected-(IC1-PF1(ADC1)-Pad60)") (class "Default")
      (node (ref "IC1") (pin "60") (pinfunction "PF1(ADC1)_60") (pintype "input"))
    )
    (net (code "76") (name "unconnected-(IC1-PF3(ADC3)-Pad58)") (class "Default")
      (node (ref "IC1") (pin "58") (pinfunction "PF3(ADC3)_58") (pintype "input"))
    )
    (net (code "77") (name "unconnected-(IC1-PF4(ADC4{slash}TCK)-Pad57)") (class "Default")
      (node (ref "IC1") (pin "57") (pinfunction "PF4(ADC4/TCK)_57") (pintype "input"))
    )
    (net (code "78") (name "unconnected-(IC1-PF5(ADC5{slash}TMS)-Pad56)") (class "Default")
      (node (ref "IC1") (pin "56") (pinfunction "PF5(ADC5/TMS)_56") (pintype "input"))
    )
    (net (code "79") (name "unconnected-(IC1-PF6(ADC6{slash}TDO)-Pad55)") (class "Default")
      (node (ref "IC1") (pin "55") (pinfunction "PF6(ADC6/TDO)_55") (pintype "input"))
    )
    (net (code "80") (name "unconnected-(IC1-PF7(ADC7{slash}TDI)-Pad54)") (class "Default")
      (node (ref "IC1") (pin "54") (pinfunction "PF7(ADC7/TDI)_54") (pintype "input"))
    )
    (net (code "81") (name "unconnected-(IC1-PG0(WR)-Pad33)") (class "Default")
      (node (ref "IC1") (pin "33") (pinfunction "PG0(WR)_33") (pintype "bidirectional"))
    )
    (net (code "82") (name "unconnected-(IC1-PG1(RD)-Pad34)") (class "Default")
      (node (ref "IC1") (pin "34") (pinfunction "PG1(RD)_34") (pintype "bidirectional"))
    )
    (net (code "83") (name "unconnected-(IC1-PG2(ALE)-Pad43)") (class "Default")
      (node (ref "IC1") (pin "43") (pinfunction "PG2(ALE)_43") (pintype "bidirectional"))
    )
    (net (code "84") (name "unconnected-(IC1-PG3(TOSC2)-Pad18)") (class "Default")
      (node (ref "IC1") (pin "18") (pinfunction "PG3(TOSC2)_18") (pintype "bidirectional"))
    )
    (net (code "85") (name "unconnected-(IC1-PG4(TOSC1)-Pad19)") (class "Default")
      (node (ref "IC1") (pin "19") (pinfunction "PG4(TOSC1)_19") (pintype "bidirectional"))
    )
    (net (code "86") (name "unconnected-(IC2-3V3OUT-Pad17)") (class "Default")
      (node (ref "IC2") (pin "17") (pinfunction "3V3OUT_17") (pintype "output"))
    )
    (net (code "87") (name "unconnected-(IC2-CBUS2-Pad13)") (class "Default")
      (node (ref "IC2") (pin "13") (pinfunction "CBUS2_13") (pintype "bidirectional"))
    )
    (net (code "88") (name "unconnected-(IC2-CBUS3-Pad14)") (class "Default")
      (node (ref "IC2") (pin "14") (pinfunction "CBUS3_14") (pintype "bidirectional"))
    )
    (net (code "89") (name "unconnected-(IC2-CBUS4-Pad12)") (class "Default")
      (node (ref "IC2") (pin "12") (pinfunction "CBUS4_12") (pintype "bidirectional"))
    )
    (net (code "90") (name "unconnected-(IC2-OSCI-Pad27)") (class "Default")
      (node (ref "IC2") (pin "27") (pinfunction "OSCI_27") (pintype "input"))
    )
    (net (code "91") (name "unconnected-(IC2-OSCO-Pad28)") (class "Default")
      (node (ref "IC2") (pin "28") (pinfunction "OSCO_28") (pintype "output"))
    )
    (net (code "92") (name "unconnected-(IC2-~{CTS}-Pad11)") (class "Default")
      (node (ref "IC2") (pin "11") (pinfunction "~{CTS}_11") (pintype "input"))
    )
    (net (code "93") (name "unconnected-(IC2-~{DCD}-Pad10)") (class "Default")
      (node (ref "IC2") (pin "10") (pinfunction "~{DCD}_10") (pintype "input"))
    )
    (net (code "94") (name "unconnected-(IC2-~{DSR}-Pad9)") (class "Default")
      (node (ref "IC2") (pin "9") (pinfunction "~{DSR}_9") (pintype "input"))
    )
    (net (code "95") (name "unconnected-(IC2-~{RESET}-Pad19)") (class "Default")
      (node (ref "IC2") (pin "19") (pinfunction "~{RESET}_19") (pintype "input"))
    )
    (net (code "96") (name "unconnected-(IC2-~{RI}-Pad6)") (class "Default")
      (node (ref "IC2") (pin "6") (pinfunction "~{RI}_6") (pintype "input"))
    )
    (net (code "97") (name "unconnected-(IC2-~{RTS}-Pad3)") (class "Default")
      (node (ref "IC2") (pin "3") (pinfunction "~{RTS}_3") (pintype "output"))
    )
    (net (code "98") (name "unconnected-(J2-DAT1-Pad8)") (class "Default")
      (node (ref "J2") (pin "8") (pinfunction "DAT1_8") (pintype "bidirectional"))
    )
    (net (code "99") (name "unconnected-(J2-DATA2-Pad1)") (class "Default")
      (node (ref "J2") (pin "1") (pinfunction "DATA2_1") (pintype "bidirectional"))
    )
    (net (code "100") (name "unconnected-(J2-DETECT-PadDT)") (class "Default")
      (node (ref "J2") (pin "DT") (pinfunction "DETECT_DT") (pintype "bidirectional"))
    )
    (net (code "101") (name "unconnected-(J2-SWITCH-PadSW)") (class "Default")
      (node (ref "J2") (pin "SW") (pinfunction "SWITCH_SW") (pintype "bidirectional"))
    )
    (net (code "102") (name "unconnected-(J3-ID-Pad4)") (class "Default")
      (node (ref "J3") (pin "4") (pinfunction "ID_4") (pintype "passive"))
    )
    (net (code "103") (name "unconnected-(U1-INT2-Pad5)") (class "Default")
      (node (ref "U1") (pin "5") (pinfunction "INT2_5") (pintype "bidirectional"))
    )
    (net (code "104") (name "unconnected-(U3-DNC-Pad2)") (class "Default")
      (node (ref "U3") (pin "2") (pinfunction "DNC_2") (pintype "bidirectional"))
    )
    (net (code "105") (name "unconnected-(U3-GPIO2-Pad9)") (class "Default")
      (node (ref "U3") (pin "9") (pinfunction "GPIO2_9") (pintype "bidirectional"))
    )
    (net (code "106") (name "unconnected-(U4-INT2-Pad9)") (class "Default")
      (node (ref "U4") (pin "9") (pinfunction "INT2_9") (pintype "bidirectional"))
    )
    (net (code "107") (name "unconnected-(XB1-AD0{slash}DIO0-Pad20)") (class "Default")
      (node (ref "XB1") (pin "20") (pinfunction "AD0/DIO0_20") (pintype "bidirectional"))
    )
    (net (code "108") (name "unconnected-(XB1-AD1{slash}DIO1-Pad19)") (class "Default")
      (node (ref "XB1") (pin "19") (pinfunction "AD1/DIO1_19") (pintype "bidirectional"))
    )
    (net (code "109") (name "unconnected-(XB1-AD2{slash}DIO2-Pad18)") (class "Default")
      (node (ref "XB1") (pin "18") (pinfunction "AD2/DIO2_18") (pintype "bidirectional"))
    )
    (net (code "110") (name "unconnected-(XB1-ASSOC{slash}AD5{slash}DIO5-Pad15)") (class "Default")
      (node (ref "XB1") (pin "15") (pinfunction "ASSOC/AD5/DIO5_15") (pintype "bidirectional"))
    )
    (net (code "111") (name "unconnected-(XB1-CD{slash}DOUT_EN{slash}DO8-Pad4)") (class "Default")
      (node (ref "XB1") (pin "4") (pinfunction "CD/DOUT_EN/DO8_4") (pintype "output"))
    )
    (net (code "112") (name "unconnected-(XB1-COORD_SEL{slash}AD3{slash}DIO3-Pad17)") (class "Default")
      (node (ref "XB1") (pin "17") (pinfunction "COORD_SEL/AD3/DIO3_17") (pintype "bidirectional"))
    )
    (net (code "113") (name "unconnected-(XB1-ON{slash}~{SLEEP}-Pad13)") (class "Default")
      (node (ref "XB1") (pin "13") (pinfunction "ON/~{SLEEP}_13") (pintype "output"))
    )
    (net (code "114") (name "unconnected-(XB1-PWM0{slash}RSSI-Pad6)") (class "Default")
      (node (ref "XB1") (pin "6") (pinfunction "PWM0/RSSI_6") (pintype "output"))
    )
    (net (code "115") (name "unconnected-(XB1-RF_TX{slash}AD4{slash}DIO4-Pad11)") (class "Default")
      (node (ref "XB1") (pin "11") (pinfunction "RF_TX/AD4/DIO4_11") (pintype "bidirectional"))
    )
    (net (code "116") (name "unconnected-(XB1-VREF-Pad14)") (class "Default")
      (node (ref "XB1") (pin "14") (pinfunction "VREF_14") (pintype "input"))
    )
    (net (code "117") (name "unconnected-(XB1-~{CTS}{slash}DIO7-Pad12)") (class "Default")
      (node (ref "XB1") (pin "12") (pinfunction "~{CTS}/DIO7_12") (pintype "bidirectional"))
    )
    (net (code "118") (name "unconnected-(XB1-~{RTS}{slash}AD6{slash}DIO6-Pad16)") (class "Default")
      (node (ref "XB1") (pin "16") (pinfunction "~{RTS}/AD6/DIO6_16") (pintype "bidirectional"))
    )
    (net (code "119") (name "~{GPS_SLP}") (class "Default")
      (node (ref "GPS1") (pin "26") (pinfunction "HW_S_26") (pintype "bidirectional"))
      (node (ref "IC1") (pin "29") (pinfunction "(IC1)PD4_29") (pintype "bidirectional"))
    )
    (net (code "120") (name "~{RST}") (class "Default")
      (node (ref "C14") (pin "2") (pinfunction "2_2") (pintype "passive"))
      (node (ref "IC1") (pin "20") (pinfunction "RESET_20") (pintype "input"))
      (node (ref "JP1") (pin "5") (pinfunction "5_5") (pintype "passive"))
      (node (ref "R1") (pin "2") (pinfunction "2_2") (pintype "passive"))
      (node (ref "S1") (pin "P2@1") (pinfunction "1_P2@1") (pintype "passive"))
      (node (ref "S1") (pin "P2@2") (pinfunction "1_P2@2") (pintype "passive"))
    )
  )
)
